# DSO_RAM.net
KiCad netlist of a schematic drawn in Altium Designer
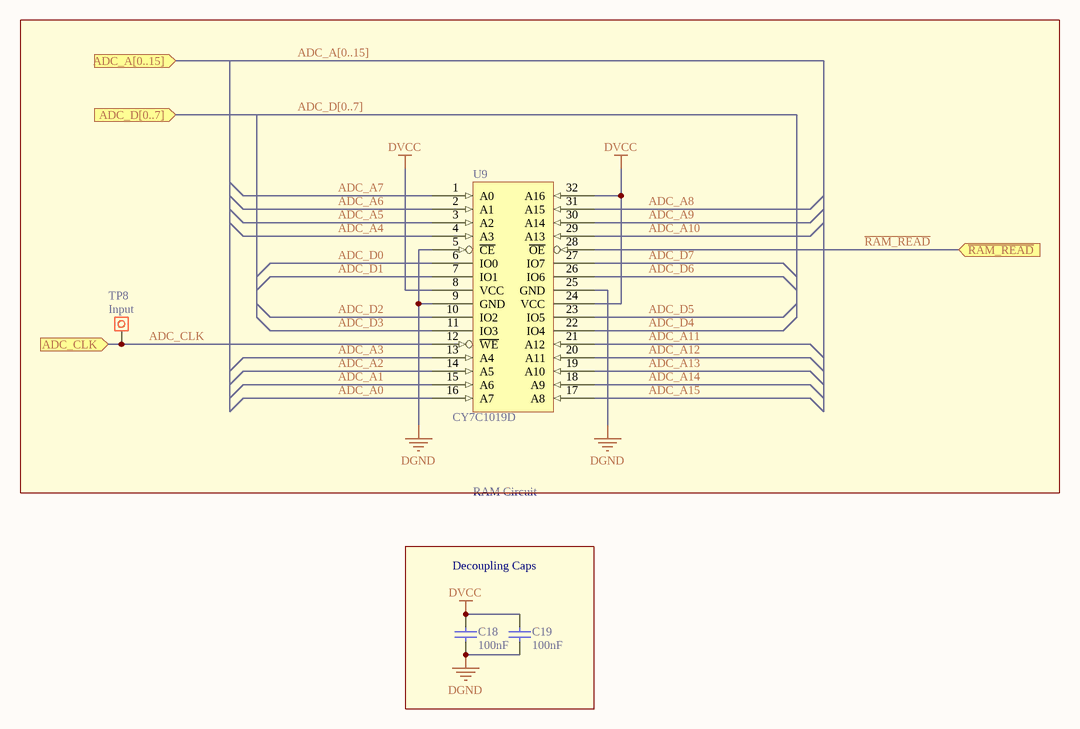
[diagram p0: DSO_RAM.SchDoc]

(export (version "E")
  (design (tool "Eeschema 10.0.6"))
  (components
    (comp (ref "C18")
      (value "100nF")
      (footprint "0805C")
      (description "Capacitor")
      (fields (field (name "REVIEWED BY") "RM - 2018/08/05"))
      (libsource (lib "DSO") (part "C"))
    )
    (comp (ref "C19")
      (value "100nF")
      (footprint "0805C")
      (description "Capacitor")
      (fields (field (name "REVIEWED BY") "RM - 2018/08/05"))
      (libsource (lib "DSO") (part "C"))
    )
    (comp (ref "TP8")
      (value "Input")
      (footprint "Testpoin")
      (description "Pad")
      (fields (field (name "Comment") "INPUT"))
      (libsource (lib "DSO") (part "Test Point"))
    )
    (comp (ref "U9")
      (value "CY7C1019D")
      (footprint "TSOP-32")
      (description "SRAM 128k x 8")
      (fields (field (name "REVIEWED BY") "RM - 2018/08/05"))
      (libsource (lib "DSO") (part "CY7C1019D"))
    )
  )
  (nets
    (net (code "1") (name "/ADC_A0") (class "Default")
      (node (ref "U9") (pin "16") (pinfunction "A7_16") (pintype "input"))
    )
    (net (code "2") (name "/ADC_A1") (class "Default")
      (node (ref "U9") (pin "15") (pinfunction "A6_15") (pintype "input"))
    )
    (net (code "3") (name "/ADC_A2") (class "Default")
      (node (ref "U9") (pin "14") (pinfunction "A5_14") (pintype "input"))
    )
    (net (code "4") (name "/ADC_A3") (class "Default")
      (node (ref "U9") (pin "13") (pinfunction "A4_13") (pintype "input"))
    )
    (net (code "5") (name "/ADC_A4") (class "Default")
      (node (ref "U9") (pin "4") (pinfunction "A3_4") (pintype "input"))
    )
    (net (code "6") (name "/ADC_A5") (class "Default")
      (node (ref "U9") (pin "3") (pinfunction "A2_3") (pintype "input"))
    )
    (net (code "7") (name "/ADC_A6") (class "Default")
      (node (ref "U9") (pin "2") (pinfunction "A1_2") (pintype "input"))
    )
    (net (code "8") (name "/ADC_A7") (class "Default")
      (node (ref "U9") (pin "1") (pinfunction "A0_1") (pintype "input"))
    )
    (net (code "9") (name "/ADC_A8") (class "Default")
      (node (ref "U9") (pin "31") (pinfunction "A15_31") (pintype "input"))
    )
    (net (code "10") (name "/ADC_A9") (class "Default")
      (node (ref "U9") (pin "30") (pinfunction "A14_30") (pintype "input"))
    )
    (net (code "11") (name "/ADC_A10") (class "Default")
      (node (ref "U9") (pin "29") (pinfunction "A13_29") (pintype "input"))
    )
    (net (code "12") (name "/ADC_A11") (class "Default")
      (node (ref "U9") (pin "21") (pinfunction "A12_21") (pintype "input"))
    )
    (net (code "13") (name "/ADC_A12") (class "Default")
      (node (ref "U9") (pin "20") (pinfunction "A11_20") (pintype "input"))
    )
    (net (code "14") (name "/ADC_A13") (class "Default")
      (node (ref "U9") (pin "19") (pinfunction "A10_19") (pintype "input"))
    )
    (net (code "15") (name "/ADC_A14") (class "Default")
      (node (ref "U9") (pin "18") (pinfunction "A9_18") (pintype "input"))
    )
    (net (code "16") (name "/ADC_A15") (class "Default")
      (node (ref "U9") (pin "17") (pinfunction "A8_17") (pintype "input"))
    )
    (net (code "18") (name "/ADC_CLK") (class "Default")
      (node (ref "TP8") (pin "1") (pintype "passive"))
      (node (ref "U9") (pin "12") (pinfunction "~{WE}_12") (pintype "input"))
    )
    (net (code "19") (name "/ADC_D0") (class "Default")
      (node (ref "U9") (pin "6") (pinfunction "IO0_6") (pintype "tri_state"))
    )
    (net (code "20") (name "/ADC_D1") (class "Default")
      (node (ref "U9") (pin "7") (pinfunction "IO1_7") (pintype "tri_state"))
    )
    (net (code "21") (name "/ADC_D2") (class "Default")
      (node (ref "U9") (pin "10") (pinfunction "IO2_10") (pintype "tri_state"))
    )
    (net (code "22") (name "/ADC_D3") (class "Default")
      (node (ref "U9") (pin "11") (pinfunction "IO3_11") (pintype "tri_state"))
    )
    (net (code "23") (name "/ADC_D4") (class "Default")
      (node (ref "U9") (pin "22") (pinfunction "IO4_22") (pintype "tri_state"))
    )
    (net (code "24") (name "/ADC_D5") (class "Default")
      (node (ref "U9") (pin "23") (pinfunction "IO5_23") (pintype "tri_state"))
    )
    (net (code "25") (name "/ADC_D6") (class "Default")
      (node (ref "U9") (pin "26") (pinfunction "IO6_26") (pintype "tri_state"))
    )
    (net (code "26") (name "/ADC_D7") (class "Default")
      (node (ref "U9") (pin "27") (pinfunction "IO7_27") (pintype "tri_state"))
    )
    (net (code "28") (name "/~{RAM_READ}") (class "Default")
      (node (ref "U9") (pin "28") (pinfunction "~{OE}_28") (pintype "input"))
    )
    (net (code "29") (name "DGND") (class "Default")
      (node (ref "C18") (pin "2") (pinfunction "2_2") (pintype "passive"))
      (node (ref "C19") (pin "2") (pinfunction "2_2") (pintype "passive"))
      (node (ref "U9") (pin "25") (pinfunction "GND_25") (pintype "passive"))
      (node (ref "U9") (pin "5") (pinfunction "~{CE}_5") (pintype "input"))
      (node (ref "U9") (pin "9") (pinfunction "GND_9") (pintype "passive"))
    )
    (net (code "30") (name "DVCC") (class "Default")
      (node (ref "C18") (pin "1") (pinfunction "1_1") (pintype "passive"))
      (node (ref "C19") (pin "1") (pinfunction "1_1") (pintype "passive"))
      (node (ref "U9") (pin "24") (pinfunction "VCC_24") (pintype "passive"))
      (node (ref "U9") (pin "32") (pinfunction "A16_32") (pintype "input"))
      (node (ref "U9") (pin "8") (pinfunction "VCC_8") (pintype "passive"))
    )
  )
)
